# Sheet3.net
KiCad netlist of a schematic drawn in Altium Designer
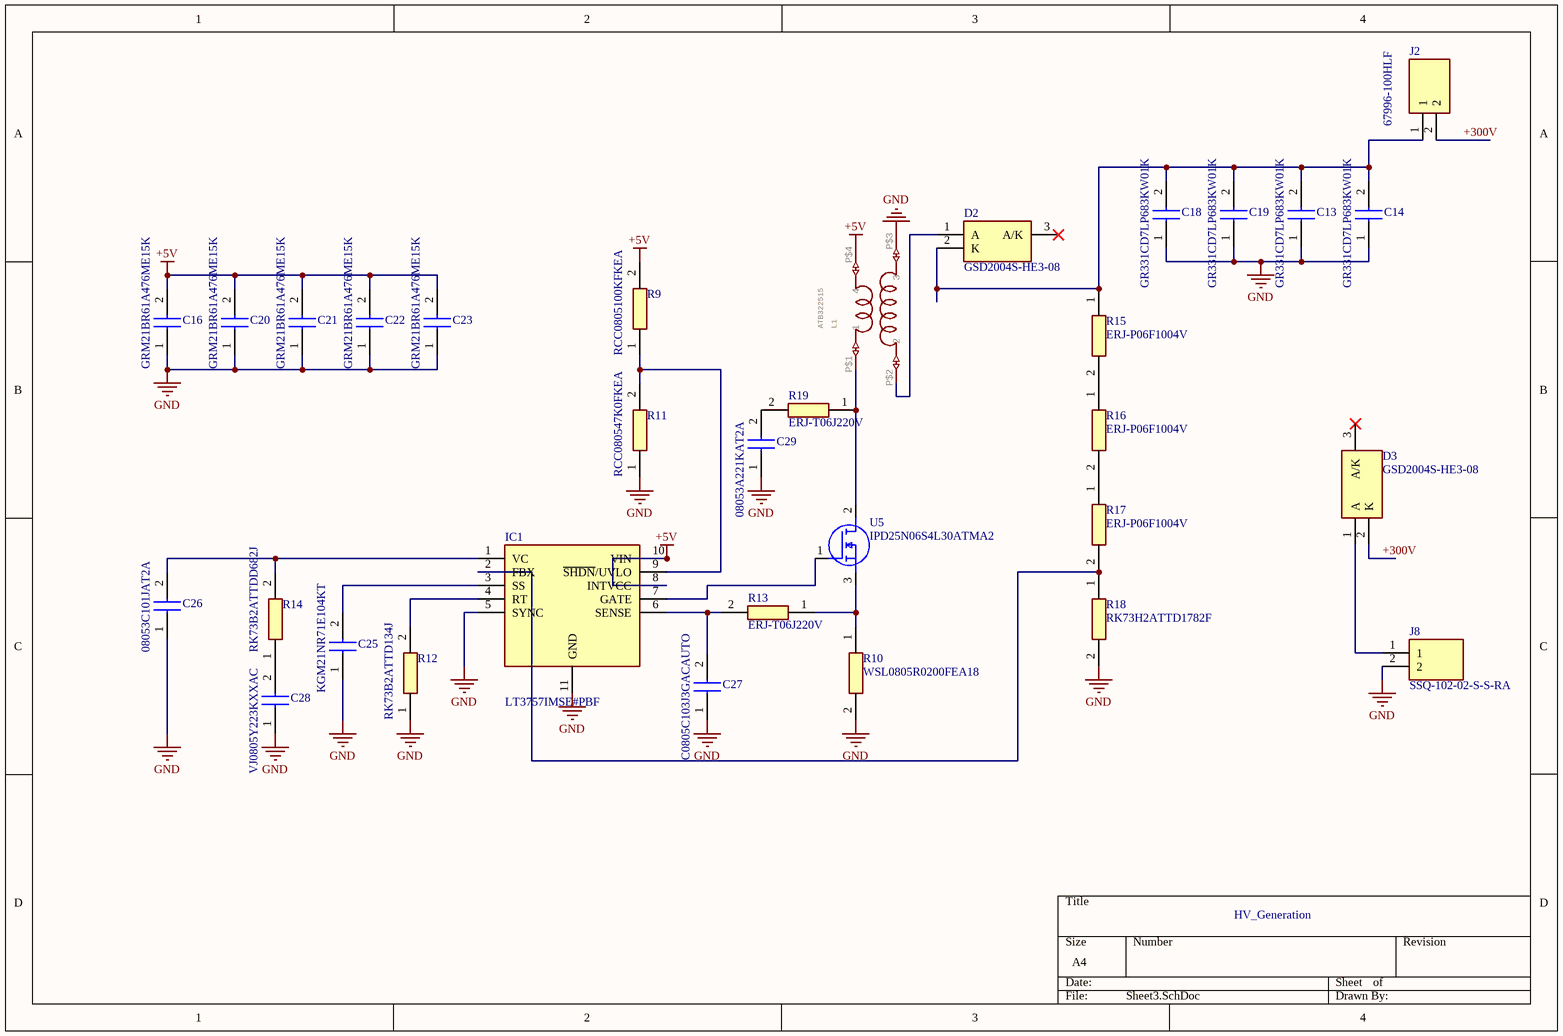
[diagram p0: Sheet3.SchDoc]

(export (version "E")
  (design (tool "Eeschema 10.0.6"))
  (components
    (comp (ref "C13")
      (value "GR331CD7LP683KW01K")
      (footprint "SamacSys:C3216_Commercial")
      (description "Capacitor")
      (fields (field (name "MANUFACTURER_PART_NUMBER") "C3216X7T2W683K130AA"))
      (libsource (lib "SamacSys") (part "C3216X7T2W683K130AA"))
    )
    (comp (ref "C14")
      (value "GR331CD7LP683KW01K")
      (footprint "SamacSys:C3216_Commercial")
      (description "Capacitor")
      (fields (field (name "MANUFACTURER_PART_NUMBER") "C3216X7T2W683K130AA"))
      (libsource (lib "SamacSys") (part "C3216X7T2W683K130AA"))
    )
    (comp (ref "C16")
      (value "GRM21BR61A476ME15K")
      (footprint "SamacSys:CAPC2012X100N")
      (description "Capacitor")
      (fields
        (field (name "MANUFACTURER_PART_NUMBER") "KGM21NR71E104KT")
        (field (name "MOUSER PART NUMBER") "581-KGM21NR71E104KT")
      )
      (libsource (lib "*") (part "KGM21NR71E104KT"))
    )
    (comp (ref "C18")
      (value "GR331CD7LP683KW01K")
      (footprint "SamacSys:C3216_Commercial")
      (description "Capacitor")
      (fields (field (name "MANUFACTURER_PART_NUMBER") "C3216X7T2W683K130AA"))
      (libsource (lib "SamacSys") (part "C3216X7T2W683K130AA"))
    )
    (comp (ref "C19")
      (value "GR331CD7LP683KW01K")
      (footprint "SamacSys:C3216_Commercial")
      (description "Capacitor")
      (fields (field (name "MANUFACTURER_PART_NUMBER") "C3216X7T2W683K130AA"))
      (libsource (lib "SamacSys") (part "C3216X7T2W683K130AA"))
    )
    (comp (ref "C20")
      (value "GRM21BR61A476ME15K")
      (footprint "SamacSys:CAPC2012X100N")
      (description "Capacitor")
      (fields
        (field (name "MANUFACTURER_PART_NUMBER") "KGM21NR71E104KT")
        (field (name "MOUSER PART NUMBER") "581-KGM21NR71E104KT")
      )
      (libsource (lib "*") (part "KGM21NR71E104KT"))
    )
    (comp (ref "C21")
      (value "GRM21BR61A476ME15K")
      (footprint "SamacSys:CAPC2012X100N")
      (description "Capacitor")
      (fields
        (field (name "MANUFACTURER_PART_NUMBER") "KGM21NR71E104KT")
        (field (name "MOUSER PART NUMBER") "581-KGM21NR71E104KT")
      )
      (libsource (lib "*") (part "KGM21NR71E104KT"))
    )
    (comp (ref "C22")
      (value "GRM21BR61A476ME15K")
      (footprint "SamacSys:CAPC2012X100N")
      (description "Capacitor")
      (fields
        (field (name "MANUFACTURER_PART_NUMBER") "KGM21NR71E104KT")
        (field (name "MOUSER PART NUMBER") "581-KGM21NR71E104KT")
      )
      (libsource (lib "*") (part "KGM21NR71E104KT"))
    )
    (comp (ref "C23")
      (value "GRM21BR61A476ME15K")
      (footprint "SamacSys:CAPC2012X100N")
      (description "Capacitor")
      (fields
        (field (name "MANUFACTURER_PART_NUMBER") "KGM21NR71E104KT")
        (field (name "MOUSER PART NUMBER") "581-KGM21NR71E104KT")
      )
      (libsource (lib "*") (part "KGM21NR71E104KT"))
    )
    (comp (ref "C25")
      (value "KGM21NR71E104KT")
      (footprint "SamacSys:CAPC2012X100N")
      (description "Capacitor")
      (fields (field (name "MOUSER PART NUMBER") "581-KGM21NR71E104KT"))
      (libsource (lib "*") (part "KGM21NR71E104KT"))
    )
    (comp (ref "C26")
      (value "08053C101JAT2A")
      (footprint "SamacSys:CAPC2012X100N")
      (description "Capacitor")
      (fields
        (field (name "MANUFACTURER_PART_NUMBER") "KGM21NR71E104KT")
        (field (name "MOUSER PART NUMBER") "581-KGM21NR71E104KT")
      )
      (libsource (lib "*") (part "KGM21NR71E104KT"))
    )
    (comp (ref "C27")
      (value "C0805C103J3GACAUTO")
      (footprint "SamacSys:CAPC2012X100N")
      (description "Capacitor")
      (fields
        (field (name "MANUFACTURER_PART_NUMBER") "KGM21NR71E104KT")
        (field (name "MOUSER PART NUMBER") "581-KGM21NR71E104KT")
      )
      (libsource (lib "*") (part "KGM21NR71E104KT"))
    )
    (comp (ref "C28")
      (value "VJ0805Y223KXXAC")
      (footprint "SamacSys:CAPC2012X100N")
      (description "Capacitor")
      (fields
        (field (name "MANUFACTURER_PART_NUMBER") "KGM21NR71E104KT")
        (field (name "MOUSER PART NUMBER") "581-KGM21NR71E104KT")
      )
      (libsource (lib "*") (part "KGM21NR71E104KT"))
    )
    (comp (ref "C29")
      (value "08053A221KAT2A")
      (footprint "SamacSys:CAPC2012X100N")
      (description "Capacitor")
      (fields
        (field (name "MANUFACTURER_PART_NUMBER") "KGM21NR71E104KT")
        (field (name "MOUSER PART NUMBER") "581-KGM21NR71E104KT")
      )
      (libsource (lib "*") (part "KGM21NR71E104KT"))
    )
    (comp (ref "D2")
      (value "GSD2004S-HE3-08")
      (footprint "SamacSys:SOT95P248X115-3N")
      (description "Diode")
      (fields (field (name "MOUSER PART NUMBER") "78-GSD2004S-HE3-08"))
      (libsource (lib "") (part "GSD2004S-HE3-08_1"))
    )
    (comp (ref "D3")
      (value "GSD2004S-HE3-08")
      (footprint "SamacSys:SOT95P248X115-3N")
      (description "Diode")
      (fields (field (name "MOUSER PART NUMBER") "78-GSD2004S-HE3-08"))
      (libsource (lib "SamacSys") (part "GSD2004S-HE3-08"))
    )
    (comp (ref "IC1")
      (value "LT3757IMSE#PBF")
      (footprint "SamacSys:SOP50P490X110-11N")
      (description "Integrated Circuit")
      (fields (field (name "MOUSER PART NUMBER") "584-LT3757IMSE#PBF"))
      (libsource (lib "*") (part "LT3757IMSE#PBF"))
    )
    (comp (ref "J2")
      (value "67996-100HLF")
      (footprint "HDRV2W67P254_2X1_254X483X858P")
      (libsource (lib "67996-100HLF") (part "67996-100HLF"))
    )
    (comp (ref "J8")
      (value "SSQ-102-02-S-S-RA")
      (footprint "SamacSys:RHDRRA2W64P254_1X2_559X851X241P")
      (description "Connector")
      (libsource (lib "*") (part "SSQ-102-02-S-S-RA"))
    )
    (comp (ref "L1")
      (value "ATB322515")
      (footprint "kajimoto:ATB322515")
      (fields (field (name "LIBRARYNAME") "kajimoto"))
      (libsource (lib "kajimoto") (part "ATB322515"))
    )
    (comp (ref "R9")
      (value "RCC0805100KFKEA")
      (footprint "SamacSys:RESC2012X60N")
      (description "Resistor")
      (fields (field (name "MANUFACTURER_PART_NUMBER") "RK73B2ATTD123J"))
      (libsource (lib "") (part "RK73B2ATTD123J_1"))
    )
    (comp (ref "R10")
      (value "WSL0805R0200FEA18")
      (footprint "SamacSys:RESC2012X60N")
      (description "Resistor")
      (fields (field (name "MANUFACTURER_PART_NUMBER") "RK73B2ATTD123J"))
      (libsource (lib "*") (part "RK73B2ATTD123J"))
    )
    (comp (ref "R11")
      (value "RCC080547K0FKEA")
      (footprint "SamacSys:RESC2012X60N")
      (description "Resistor")
      (fields (field (name "MANUFACTURER_PART_NUMBER") "RK73B2ATTD123J"))
      (libsource (lib "") (part "RK73B2ATTD123J_1"))
    )
    (comp (ref "R12")
      (value "RK73B2ATTD134J")
      (footprint "SamacSys:RESC2012X60N")
      (description "Resistor")
      (fields (field (name "MANUFACTURER_PART_NUMBER") "RK73B2ATTD123J"))
      (libsource (lib "") (part "RK73B2ATTD123J_1"))
    )
    (comp (ref "R13")
      (value "ERJ-T06J220V")
      (footprint "SamacSys:RESC2012X60N")
      (description "Resistor")
      (fields (field (name "MANUFACTURER_PART_NUMBER") "RK73B2ATTD123J"))
      (libsource (lib "") (part "RK73B2ATTD123J_2"))
    )
    (comp (ref "R14")
      (value "RK73B2ATTDD682J")
      (footprint "SamacSys:RESC2012X60N")
      (description "Resistor")
      (fields (field (name "MANUFACTURER_PART_NUMBER") "RK73B2ATTD123J"))
      (libsource (lib "") (part "RK73B2ATTD123J_1"))
    )
    (comp (ref "R15")
      (value "ERJ-P06F1004V")
      (footprint "SamacSys:RESC2012X60N")
      (description "Resistor")
      (fields (field (name "MANUFACTURER_PART_NUMBER") "RK73B2ATTD123J"))
      (libsource (lib "*") (part "RK73B2ATTD123J"))
    )
    (comp (ref "R16")
      (value "ERJ-P06F1004V")
      (footprint "SamacSys:RESC2012X60N")
      (description "Resistor")
      (fields (field (name "MANUFACTURER_PART_NUMBER") "RK73B2ATTD123J"))
      (libsource (lib "*") (part "RK73B2ATTD123J"))
    )
    (comp (ref "R17")
      (value "ERJ-P06F1004V")
      (footprint "SamacSys:RESC2012X60N")
      (description "Resistor")
      (fields (field (name "MANUFACTURER_PART_NUMBER") "RK73B2ATTD123J"))
      (libsource (lib "*") (part "RK73B2ATTD123J"))
    )
    (comp (ref "R18")
      (value "RK73H2ATTD1782F")
      (footprint "SamacSys:RESC2012X60N")
      (description "Resistor")
      (fields (field (name "MANUFACTURER_PART_NUMBER") "RK73B2ATTD123J"))
      (libsource (lib "*") (part "RK73B2ATTD123J"))
    )
    (comp (ref "R19")
      (value "ERJ-T06J220V")
      (footprint "SamacSys:RESC2012X60N")
      (description "Resistor")
      (fields (field (name "MANUFACTURER_PART_NUMBER") "RK73B2ATTD123J"))
      (libsource (lib "") (part "RK73B2ATTD123J_2"))
    )
    (comp (ref "U5")
      (value "IPD25N06S4L30ATMA2")
      (footprint "SamacSys:IPD25N06S4L30ATMA2")
      (description "Trans MOSFET N-CH 60V 25A Automotive 3-Pin(2+Tab) DPAK T/R002")
      (libsource (lib "SamacSys") (part "IPD25N06S4L30ATMA2"))
    )
  )
  (nets
    (net (code "1") (name "+5V") (class "Default")
      (node (ref "C16") (pin "2") (pinfunction "2_2") (pintype "passive"))
      (node (ref "C20") (pin "2") (pinfunction "2_2") (pintype "passive"))
      (node (ref "C21") (pin "2") (pinfunction "2_2") (pintype "passive"))
      (node (ref "C22") (pin "2") (pinfunction "2_2") (pintype "passive"))
      (node (ref "C23") (pin "2") (pinfunction "2_2") (pintype "passive"))
      (node (ref "IC1") (pin "10") (pinfunction "VIN_10") (pintype "passive"))
      (node (ref "IC1") (pin "8") (pinfunction "INTVCC_8") (pintype "passive"))
      (node (ref "L1") (pin "P$4") (pinfunction "4_P$4") (pintype "bidirectional"))
      (node (ref "R9") (pin "2") (pinfunction "2_2") (pintype "passive"))
    )
    (net (code "2") (name "/+300V") (class "Default")
      (node (ref "D3") (pin "2") (pinfunction "K_2") (pintype "passive"))
      (node (ref "J2") (pin "2") (pinfunction "2_2") (pintype "passive"))
    )
    (net (code "4") (name "GND") (class "Default")
      (node (ref "C13") (pin "1") (pinfunction "1_1") (pintype "passive"))
      (node (ref "C14") (pin "1") (pinfunction "1_1") (pintype "passive"))
      (node (ref "C16") (pin "1") (pinfunction "1_1") (pintype "passive"))
      (node (ref "C18") (pin "1") (pinfunction "1_1") (pintype "passive"))
      (node (ref "C19") (pin "1") (pinfunction "1_1") (pintype "passive"))
      (node (ref "C20") (pin "1") (pinfunction "1_1") (pintype "passive"))
      (node (ref "C21") (pin "1") (pinfunction "1_1") (pintype "passive"))
      (node (ref "C22") (pin "1") (pinfunction "1_1") (pintype "passive"))
      (node (ref "C23") (pin "1") (pinfunction "1_1") (pintype "passive"))
      (node (ref "C25") (pin "1") (pinfunction "1_1") (pintype "passive"))
      (node (ref "C26") (pin "1") (pinfunction "1_1") (pintype "passive"))
      (node (ref "C27") (pin "1") (pinfunction "1_1") (pintype "passive"))
      (node (ref "C28") (pin "1") (pinfunction "1_1") (pintype "passive"))
      (node (ref "C29") (pin "1") (pinfunction "1_1") (pintype "passive"))
      (node (ref "IC1") (pin "11") (pinfunction "GND_11") (pintype "passive"))
      (node (ref "IC1") (pin "5") (pinfunction "SYNC_5") (pintype "passive"))
      (node (ref "J8") (pin "2") (pinfunction "2_2") (pintype "passive"))
      (node (ref "L1") (pin "P$3") (pinfunction "3_P$3") (pintype "bidirectional"))
      (node (ref "R10") (pin "2") (pinfunction "2_2") (pintype "passive"))
      (node (ref "R11") (pin "1") (pinfunction "1_1") (pintype "passive"))
      (node (ref "R12") (pin "1") (pinfunction "1_1") (pintype "passive"))
      (node (ref "R18") (pin "2") (pinfunction "2_2") (pintype "passive"))
    )
    (net (code "5") (name "Net-(C28-Pad2)") (class "Default")
      (node (ref "C28") (pin "2") (pinfunction "2_2") (pintype "passive"))
      (node (ref "R14") (pin "1") (pinfunction "1_1") (pintype "passive"))
    )
    (net (code "6") (name "Net-(C29-Pad2)") (class "Default")
      (node (ref "C29") (pin "2") (pinfunction "2_2") (pintype "passive"))
      (node (ref "R19") (pin "2") (pinfunction "2_2") (pintype "passive"))
    )
    (net (code "7") (name "Net-(D2-A)") (class "Default")
      (node (ref "D2") (pin "1") (pinfunction "A_1") (pintype "passive"))
      (node (ref "L1") (pin "P$2") (pinfunction "2_P$2") (pintype "bidirectional"))
    )
    (net (code "8") (name "Net-(D2-K)") (class "Default")
      (node (ref "C13") (pin "2") (pinfunction "2_2") (pintype "passive"))
      (node (ref "C14") (pin "2") (pinfunction "2_2") (pintype "passive"))
      (node (ref "C18") (pin "2") (pinfunction "2_2") (pintype "passive"))
      (node (ref "C19") (pin "2") (pinfunction "2_2") (pintype "passive"))
      (node (ref "D2") (pin "2") (pinfunction "K_2") (pintype "passive"))
      (node (ref "J2") (pin "1") (pinfunction "1_1") (pintype "passive"))
      (node (ref "R15") (pin "1") (pinfunction "1_1") (pintype "passive"))
    )
    (net (code "9") (name "Net-(D3-A)") (class "Default")
      (node (ref "D3") (pin "1") (pinfunction "A_1") (pintype "passive"))
      (node (ref "J8") (pin "1") (pinfunction "1_1") (pintype "passive"))
    )
    (net (code "10") (name "Net-(IC1-FBX)") (class "Default")
      (node (ref "IC1") (pin "2") (pinfunction "FBX_2") (pintype "passive"))
      (node (ref "R17") (pin "2") (pinfunction "2_2") (pintype "passive"))
      (node (ref "R18") (pin "1") (pinfunction "1_1") (pintype "passive"))
    )
    (net (code "11") (name "Net-(IC1-GATE)") (class "Default")
      (node (ref "IC1") (pin "7") (pinfunction "GATE_7") (pintype "passive"))
      (node (ref "U5") (pin "1") (pinfunction "G_1") (pintype "passive"))
    )
    (net (code "12") (name "Net-(IC1-RT)") (class "Default")
      (node (ref "IC1") (pin "4") (pinfunction "RT_4") (pintype "passive"))
      (node (ref "R12") (pin "2") (pinfunction "2_2") (pintype "passive"))
    )
    (net (code "13") (name "Net-(IC1-SENSE)") (class "Default")
      (node (ref "C27") (pin "2") (pinfunction "2_2") (pintype "passive"))
      (node (ref "IC1") (pin "6") (pinfunction "SENSE_6") (pintype "passive"))
      (node (ref "R13") (pin "2") (pinfunction "2_2") (pintype "passive"))
    )
    (net (code "14") (name "Net-(IC1-SS)") (class "Default")
      (node (ref "C25") (pin "2") (pinfunction "2_2") (pintype "passive"))
      (node (ref "IC1") (pin "3") (pinfunction "SS_3") (pintype "passive"))
    )
    (net (code "15") (name "Net-(IC1-VC)") (class "Default")
      (node (ref "C26") (pin "2") (pinfunction "2_2") (pintype "passive"))
      (node (ref "IC1") (pin "1") (pinfunction "VC_1") (pintype "passive"))
      (node (ref "R14") (pin "2") (pinfunction "2_2") (pintype "passive"))
    )
    (net (code "16") (name "Net-(IC1-~{SHDN}{slash}UVLO)") (class "Default")
      (node (ref "IC1") (pin "9") (pinfunction "~{SHDN}/UVLO_9") (pintype "passive"))
      (node (ref "R11") (pin "2") (pinfunction "2_2") (pintype "passive"))
      (node (ref "R9") (pin "1") (pinfunction "1_1") (pintype "passive"))
    )
    (net (code "17") (name "Net-(L1-1)") (class "Default")
      (node (ref "L1") (pin "P$1") (pinfunction "1_P$1") (pintype "bidirectional"))
      (node (ref "R19") (pin "1") (pinfunction "1_1") (pintype "passive"))
      (node (ref "U5") (pin "2") (pinfunction "D_2") (pintype "passive"))
    )
    (net (code "18") (name "Net-(R15-Pad2)") (class "Default")
      (node (ref "R15") (pin "2") (pinfunction "2_2") (pintype "passive"))
      (node (ref "R16") (pin "1") (pinfunction "1_1") (pintype "passive"))
    )
    (net (code "19") (name "Net-(R16-Pad2)") (class "Default")
      (node (ref "R16") (pin "2") (pinfunction "2_2") (pintype "passive"))
      (node (ref "R17") (pin "1") (pinfunction "1_1") (pintype "passive"))
    )
    (net (code "20") (name "Net-(U5-S)") (class "Default")
      (node (ref "R10") (pin "1") (pinfunction "1_1") (pintype "passive"))
      (node (ref "R13") (pin "1") (pinfunction "1_1") (pintype "passive"))
      (node (ref "U5") (pin "3") (pinfunction "S_3") (pintype "passive"))
    )
    (net (code "21") (name "unconnected-(D2-A{slash}K-Pad3)") (class "Default")
      (node (ref "D2") (pin "3") (pinfunction "A/K_3") (pintype "passive+no_connect"))
    )
    (net (code "22") (name "unconnected-(D3-A{slash}K-Pad3)") (class "Default")
      (node (ref "D3") (pin "3") (pinfunction "A/K_3") (pintype "passive+no_connect"))
    )
  )
)
